# ADC_Driver.net
KiCad netlist of a schematic drawn in Altium Designer
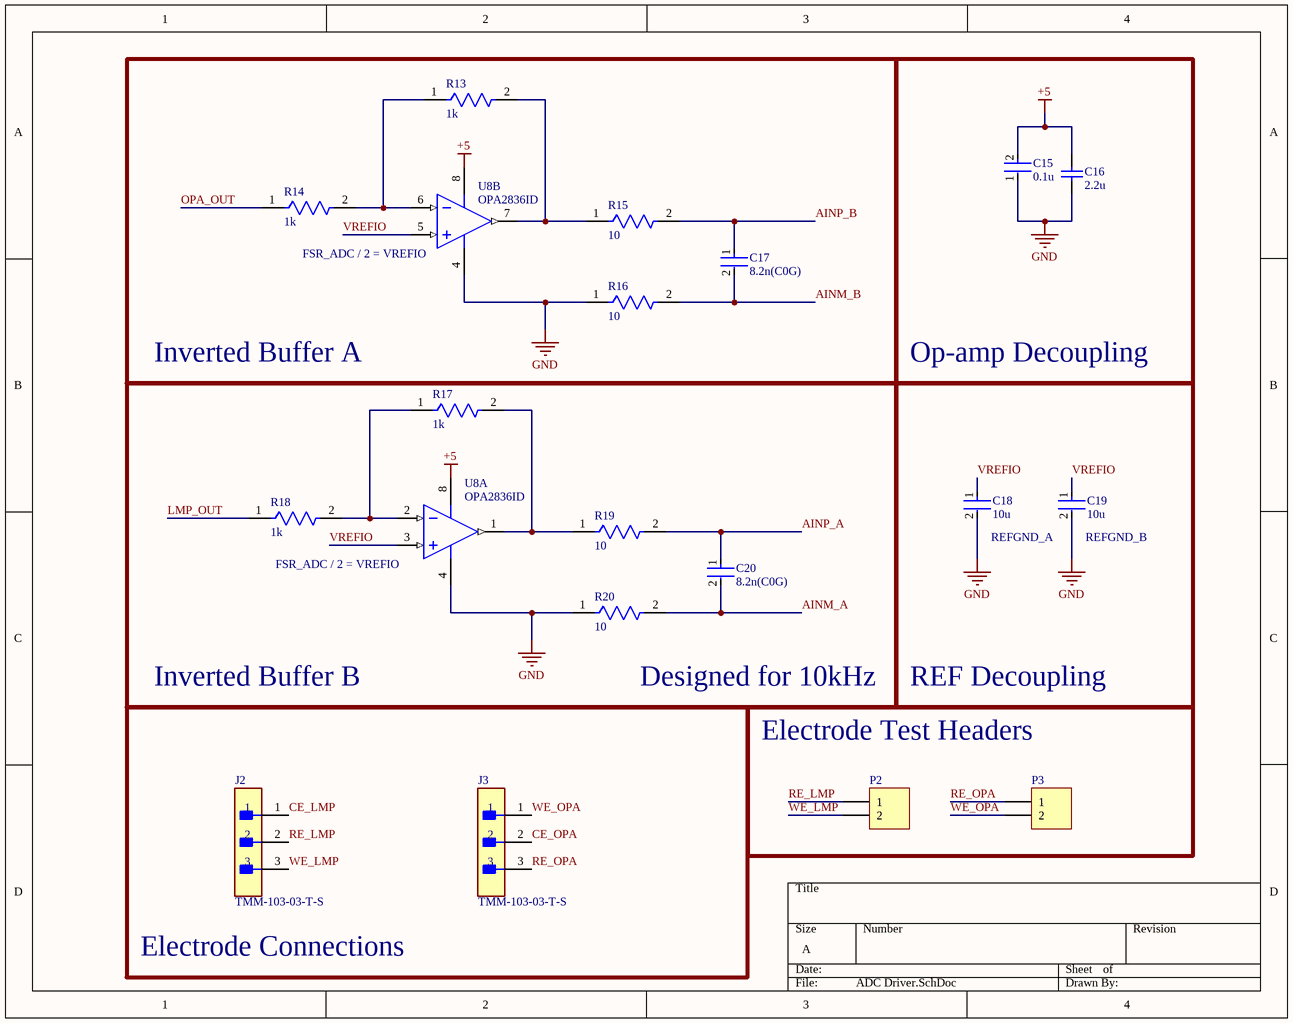
[diagram p0: ADC Driver.SchDoc]

(export (version "E")
  (design (tool "Eeschema 10.0.6"))
  (components
    (comp (ref "C15")
      (value "0.1u")
      (footprint "FP-GCJ188-0_2-IPC_C")
      (description "Cap Ceramic 0.1uF 50V X7R 10% Pad SMD 0603 Soft Termination +125°C Automotive T/R")
      (fields (field (name "TOLERANCE") "10%"))
      (libsource (lib "Altium Content Vault") (part "f23184f103b6ebe33a8c269c53dcba6"))
    )
    (comp (ref "C16")
      (value "2.2u")
      (footprint "CAPC0603(1608)100_N")
      (description "CAP 2.2uF 16V -20% to +80% 0603 (1608 Metric) Thickness 1mm SMD")
      (fields (field (name "TOLERANCE") "-20% to +80%"))
      (libsource (lib "Altium Content Vault") (part "CAP"))
    )
    (comp (ref "C17")
      (value "8.2n(C0G)")
      (footprint "FP-C2012-125-0_2-MFG")
      (description "Multilayer Ceramic Capacitors 8.2nF ±5% 250V C0G SMD 0805")
      (fields (field (name "TOLERANCE") "5%"))
      (libsource (lib "Altium Content Vault") (part "b4654b650e69147ec39a6b967a45e02"))
    )
    (comp (ref "C18")
      (value "10u")
      (footprint "FP-CL21-IPC_C")
      (description "CL21 Series 0805 10uF 6.3V ±10% Tolerance X7R Multilayer Ceramic Chip Capacitor")
      (fields (field (name "TOLERANCE") "10%") (field (name "VOLTAGE") "6.3V"))
      (libsource (lib "Altium Content Vault") (part "b4654b650e69147ec39a6b967a45e02"))
    )
    (comp (ref "C19")
      (value "10u")
      (footprint "FP-CL21-IPC_C")
      (description "CL21 Series 0805 10uF 6.3V ±10% Tolerance X7R Multilayer Ceramic Chip Capacitor")
      (fields (field (name "TOLERANCE") "10%") (field (name "VOLTAGE") "6.3V"))
      (libsource (lib "Altium Content Vault") (part "b4654b650e69147ec39a6b967a45e02"))
    )
    (comp (ref "C20")
      (value "8.2n(C0G)")
      (footprint "FP-C2012-125-0_2-MFG")
      (description "Multilayer Ceramic Capacitors 8.2nF ±5% 250V C0G SMD 0805")
      (fields (field (name "TOLERANCE") "5%"))
      (libsource (lib "Altium Content Vault") (part "b4654b650e69147ec39a6b967a45e02"))
    )
    (comp (ref "J2")
      (value "TMM-103-03-T-S")
      (footprint "FP-TMM-103-03-T-S-MFG")
      (description "CONN HEADER VERT 3POS 2MM")
      (libsource (lib "Altium Content Vault") (part "0d3f023dd272f625e17a2be33dea85f"))
    )
    (comp (ref "J3")
      (value "TMM-103-03-T-S")
      (footprint "FP-TMM-103-03-T-S-MFG")
      (description "CONN HEADER VERT 3POS 2MM")
      (libsource (lib "Altium Content Vault") (part "0d3f023dd272f625e17a2be33dea85f"))
    )
    (comp (ref "P2")
      (value "Header 2")
      (footprint "My_1X02")
      (description "Header, 2-Pin")
      (fields (field (name "ASID PART NUMBER") "Header 2-AS"))
      (libsource (lib "Mylib+Rev+4 (1)") (part "Header 2"))
    )
    (comp (ref "P3")
      (value "Header 2")
      (footprint "My_1X02")
      (description "Header, 2-Pin")
      (fields (field (name "ASID PART NUMBER") "Header 2-AS"))
      (libsource (lib "Mylib+Rev+4 (1)") (part "Header 2"))
    )
    (comp (ref "R13")
      (value "1k")
      (footprint "FP-RT0603-MFG")
      (description "RES SMD 1K OHM 0.1% 1/10W 0603")
      (fields
        (field (name "MANUFACTURER PART NUMBER") "RT0603BRD071KL")
        (field (name "MANUFACTURER") "Yageo")
      )
      (libsource (lib "Altium Content Vault") (part "1029c3af85768c4190bb7ad29bc67b5"))
    )
    (comp (ref "R14")
      (value "1k")
      (footprint "FP-RT0603-MFG")
      (description "RES SMD 1K OHM 0.1% 1/10W 0603")
      (fields
        (field (name "MANUFACTURER PART NUMBER") "RT0603BRD071KL")
        (field (name "MANUFACTURER") "Yageo")
      )
      (libsource (lib "Altium Content Vault") (part "1029c3af85768c4190bb7ad29bc67b5"))
    )
    (comp (ref "R15")
      (value "10")
      (footprint "FP-CPF0603-MFG")
      (description "RES SMD 10Ω 0.1% 1/16W 0603")
      (fields
        (field (name "MANUFACTURER") "TE Connectivity")
        (field (name "MANUFACTURER PART NUMBER") "CPF0603B10RE")
      )
      (libsource (lib "Altium Content Vault") (part "1029c3af85768c4190bb7ad29bc67b5"))
    )
    (comp (ref "R16")
      (value "10")
      (footprint "FP-CPF0603-MFG")
      (description "RES SMD 10Ω 0.1% 1/16W 0603")
      (fields
        (field (name "MANUFACTURER") "TE Connectivity")
        (field (name "MANUFACTURER PART NUMBER") "CPF0603B10RE")
      )
      (libsource (lib "Altium Content Vault") (part "1029c3af85768c4190bb7ad29bc67b5"))
    )
    (comp (ref "R17")
      (value "1k")
      (footprint "FP-RT0603-MFG")
      (description "RES SMD 1K OHM 0.1% 1/10W 0603")
      (fields
        (field (name "MANUFACTURER PART NUMBER") "RT0603BRD071KL")
        (field (name "MANUFACTURER") "Yageo")
      )
      (libsource (lib "Altium Content Vault") (part "1029c3af85768c4190bb7ad29bc67b5"))
    )
    (comp (ref "R18")
      (value "1k")
      (footprint "FP-RT0603-MFG")
      (description "RES SMD 1K OHM 0.1% 1/10W 0603")
      (fields
        (field (name "MANUFACTURER PART NUMBER") "RT0603BRD071KL")
        (field (name "MANUFACTURER") "Yageo")
      )
      (libsource (lib "Altium Content Vault") (part "1029c3af85768c4190bb7ad29bc67b5"))
    )
    (comp (ref "R19")
      (value "10")
      (footprint "FP-CPF0603-MFG")
      (description "RES SMD 10Ω 0.1% 1/16W 0603")
      (fields
        (field (name "MANUFACTURER") "TE Connectivity")
        (field (name "MANUFACTURER PART NUMBER") "CPF0603B10RE")
      )
      (libsource (lib "Altium Content Vault") (part "1029c3af85768c4190bb7ad29bc67b5"))
    )
    (comp (ref "R20")
      (value "10")
      (footprint "FP-CPF0603-MFG")
      (description "RES SMD 10Ω 0.1% 1/16W 0603")
      (fields
        (field (name "MANUFACTURER") "TE Connectivity")
        (field (name "MANUFACTURER PART NUMBER") "CPF0603B10RE")
      )
      (libsource (lib "Altium Content Vault") (part "1029c3af85768c4190bb7ad29bc67b5"))
    )
    (comp (ref "U8")
      (value "OPA2836ID")
      (footprint "D0008A_L")
      (fields (field (name "MANUFACTURER") "Texas Instruments"))
      (libsource (lib "Altium Content Vault") (part "TI-OPA2836D8"))
    )
  )
  (nets
    (net (code "1") (name "+5") (class "Default")
      (node (ref "C15") (pin "2") (pinfunction "2_2") (pintype "passive"))
      (node (ref "C16") (pin "2") (pinfunction "2_2") (pintype "passive"))
      (node (ref "U8") (pin "8") (pinfunction "VS+_8") (pintype "power_in"))
    )
    (net (code "2") (name "/AINM_A") (class "Default")
      (node (ref "C20") (pin "2") (pinfunction "2_2") (pintype "passive"))
      (node (ref "R20") (pin "2") (pinfunction "2_2") (pintype "passive"))
    )
    (net (code "3") (name "/AINM_B") (class "Default")
      (node (ref "C17") (pin "2") (pinfunction "2_2") (pintype "passive"))
      (node (ref "R16") (pin "2") (pinfunction "2_2") (pintype "passive"))
    )
    (net (code "4") (name "/AINP_A") (class "Default")
      (node (ref "C20") (pin "1") (pinfunction "1_1") (pintype "passive"))
      (node (ref "R19") (pin "2") (pinfunction "2_2") (pintype "passive"))
    )
    (net (code "5") (name "/AINP_B") (class "Default")
      (node (ref "C17") (pin "1") (pinfunction "1_1") (pintype "passive"))
      (node (ref "R15") (pin "2") (pinfunction "2_2") (pintype "passive"))
    )
    (net (code "6") (name "/CE_LMP") (class "Default")
      (node (ref "J2") (pin "1") (pinfunction "1_1") (pintype "passive"))
    )
    (net (code "7") (name "/CE_OPA") (class "Default")
      (node (ref "J3") (pin "2") (pinfunction "2_2") (pintype "passive"))
    )
    (net (code "8") (name "/LMP_OUT") (class "Default")
      (node (ref "R18") (pin "1") (pinfunction "1_1") (pintype "passive"))
    )
    (net (code "9") (name "/OPA_OUT") (class "Default")
      (node (ref "R14") (pin "1") (pinfunction "1_1") (pintype "passive"))
    )
    (net (code "10") (name "/RE_LMP") (class "Default")
      (node (ref "J2") (pin "2") (pinfunction "2_2") (pintype "passive"))
      (node (ref "P2") (pin "1") (pinfunction "1_1") (pintype "passive"))
    )
    (net (code "11") (name "/RE_OPA") (class "Default")
      (node (ref "J3") (pin "3") (pinfunction "3_3") (pintype "passive"))
      (node (ref "P3") (pin "1") (pinfunction "1_1") (pintype "passive"))
    )
    (net (code "12") (name "/VREFIO") (class "Default")
      (node (ref "C18") (pin "1") (pinfunction "1_1") (pintype "passive"))
      (node (ref "C19") (pin "1") (pinfunction "1_1") (pintype "passive"))
      (node (ref "U8") (pin "3") (pinfunction "VIN1+_3") (pintype "input"))
      (node (ref "U8") (pin "5") (pinfunction "VIN2+_5") (pintype "input"))
    )
    (net (code "13") (name "/WE_LMP") (class "Default")
      (node (ref "J2") (pin "3") (pinfunction "3_3") (pintype "passive"))
      (node (ref "P2") (pin "2") (pinfunction "2_2") (pintype "passive"))
    )
    (net (code "14") (name "/WE_OPA") (class "Default")
      (node (ref "J3") (pin "1") (pinfunction "1_1") (pintype "passive"))
      (node (ref "P3") (pin "2") (pinfunction "2_2") (pintype "passive"))
    )
    (net (code "15") (name "GND") (class "Default")
      (node (ref "C15") (pin "1") (pinfunction "1_1") (pintype "passive"))
      (node (ref "C16") (pin "1") (pinfunction "1_1") (pintype "passive"))
      (node (ref "C18") (pin "2") (pinfunction "2_2") (pintype "passive"))
      (node (ref "C19") (pin "2") (pinfunction "2_2") (pintype "passive"))
      (node (ref "R16") (pin "1") (pinfunction "1_1") (pintype "passive"))
      (node (ref "R20") (pin "1") (pinfunction "1_1") (pintype "passive"))
      (node (ref "U8") (pin "4") (pinfunction "VS-_4") (pintype "power_in"))
    )
    (net (code "16") (name "Net-(U8A-VIN1-)") (class "Default")
      (node (ref "R17") (pin "1") (pinfunction "1_1") (pintype "passive"))
      (node (ref "R18") (pin "2") (pinfunction "2_2") (pintype "passive"))
      (node (ref "U8") (pin "2") (pinfunction "VIN1-_2") (pintype "input"))
    )
    (net (code "17") (name "Net-(U8A-VOUT1)") (class "Default")
      (node (ref "R17") (pin "2") (pinfunction "2_2") (pintype "passive"))
      (node (ref "R19") (pin "1") (pinfunction "1_1") (pintype "passive"))
      (node (ref "U8") (pin "1") (pinfunction "VOUT1_1") (pintype "output"))
    )
    (net (code "18") (name "Net-(U8B-VIN2-)") (class "Default")
      (node (ref "R13") (pin "1") (pinfunction "1_1") (pintype "passive"))
      (node (ref "R14") (pin "2") (pinfunction "2_2") (pintype "passive"))
      (node (ref "U8") (pin "6") (pinfunction "VIN2-_6") (pintype "input"))
    )
    (net (code "19") (name "Net-(U8B-VOUT2)") (class "Default")
      (node (ref "R13") (pin "2") (pinfunction "2_2") (pintype "passive"))
      (node (ref "R15") (pin "1") (pinfunction "1_1") (pintype "passive"))
      (node (ref "U8") (pin "7") (pinfunction "VOUT2_7") (pintype "output"))
    )
  )
)
